# mark1.net
KiCad netlist of a schematic drawn in EAGLE
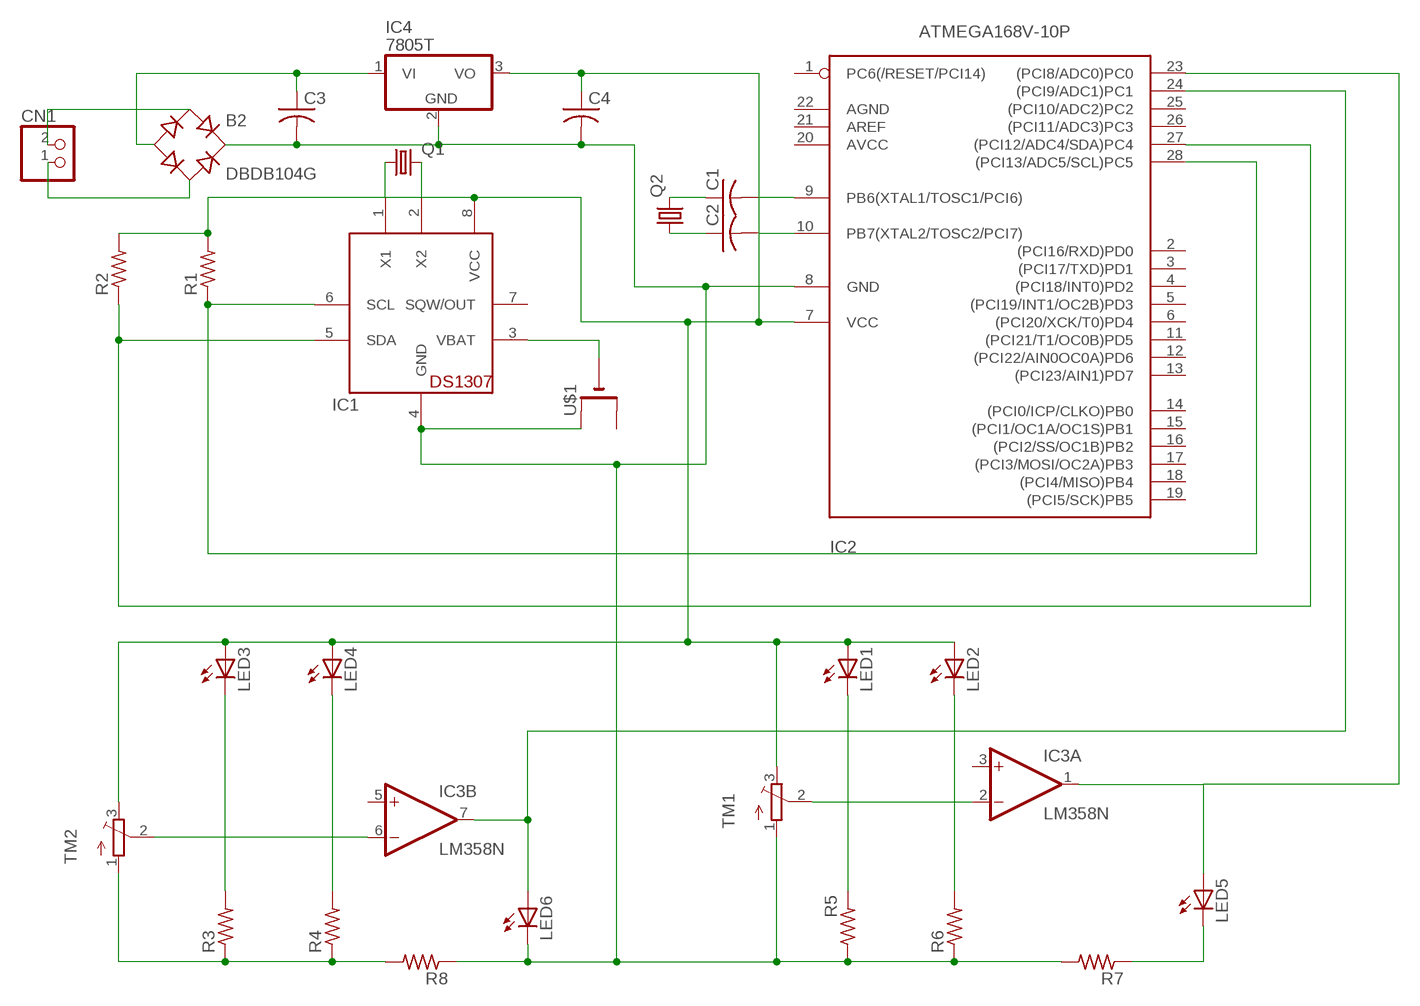
[diagram p0: schematic, sheet 1]

(export (version "E")
  (design (tool "Eeschema 10.0.6"))
  (components
    (comp (ref "B2")
      (value "DBDB104G")
      (footprint "eagle-import:DB")
      (libsource (lib "eagle-import") (part "DB?GDB104"))
    )
    (comp (ref "C1")
      (value "C-US025-024X044")
      (footprint "eagle-import:C025-024X044")
      (libsource (lib "eagle-import") (part "C-US025-024X044"))
    )
    (comp (ref "C2")
      (value "C-US025-024X044")
      (footprint "eagle-import:C025-024X044")
      (libsource (lib "eagle-import") (part "C-US025-024X044"))
    )
    (comp (ref "C3")
      (value "C-US025-024X044")
      (footprint "eagle-import:C025-024X044")
      (libsource (lib "eagle-import") (part "C-US025-024X044"))
    )
    (comp (ref "C4")
      (value "C-US025-024X044")
      (footprint "eagle-import:C025-024X044")
      (libsource (lib "eagle-import") (part "C-US025-024X044"))
    )
    (comp (ref "CN1")
      (value "JST_2PIN-THM")
      (footprint "eagle-import:JST-PH-2-THM")
      (libsource (lib "eagle-import") (part "JST_2PIN-THM"))
    )
    (comp (ref "IC1")
      (value "DS1307")
      (footprint "eagle-import:DIL08")
      (libsource (lib "eagle-import") (part "DS1307"))
    )
    (comp (ref "IC2")
      (value "ATMEGA168V-10P")
      (footprint "eagle-import:DIL28-3")
      (libsource (lib "eagle-import") (part "ATMEGA168PV-10"))
    )
    (comp (ref "IC3")
      (value "LM358N")
      (footprint "eagle-import:DIL08")
      (libsource (lib "eagle-import") (part "LM358N"))
    )
    (comp (ref "IC4")
      (value "7805T")
      (footprint "eagle-import:TO220H")
      (libsource (lib "eagle-import") (part "78T05"))
    )
    (comp (ref "LED1")
      (value "LED5MM")
      (footprint "eagle-import:LED5MM")
      (libsource (lib "eagle-import") (part "LED5MM"))
    )
    (comp (ref "LED2")
      (value "LED5MM")
      (footprint "eagle-import:LED5MM")
      (libsource (lib "eagle-import") (part "LED5MM"))
    )
    (comp (ref "LED3")
      (value "LED5MM")
      (footprint "eagle-import:LED5MM")
      (libsource (lib "eagle-import") (part "LED5MM"))
    )
    (comp (ref "LED4")
      (value "LED5MM")
      (footprint "eagle-import:LED5MM")
      (libsource (lib "eagle-import") (part "LED5MM"))
    )
    (comp (ref "LED5")
      (value "LED5MM")
      (footprint "eagle-import:LED5MM")
      (libsource (lib "eagle-import") (part "LED5MM"))
    )
    (comp (ref "LED6")
      (value "LED5MM")
      (footprint "eagle-import:LED5MM")
      (libsource (lib "eagle-import") (part "LED5MM"))
    )
    (comp (ref "Q1")
      (value "CRYSTALTC26V")
      (footprint "eagle-import:TC26V")
      (libsource (lib "eagle-import") (part "CRYSTALTC26V"))
    )
    (comp (ref "Q2")
      (value "CRYSTALHC33U-V")
      (footprint "eagle-import:HC33U-V")
      (libsource (lib "eagle-import") (part "CRYSTALHC33U-V"))
    )
    (comp (ref "R1")
      (value "R-US_0204/7")
      (footprint "eagle-import:0204_7")
      (libsource (lib "eagle-import") (part "R-US_0204/7"))
    )
    (comp (ref "R2")
      (value "R-US_0204/7")
      (footprint "eagle-import:0204_7")
      (libsource (lib "eagle-import") (part "R-US_0204/7"))
    )
    (comp (ref "R3")
      (value "R-US_0204/7")
      (footprint "eagle-import:0204_7")
      (libsource (lib "eagle-import") (part "R-US_0204/7"))
    )
    (comp (ref "R4")
      (value "R-US_0204/7")
      (footprint "eagle-import:0204_7")
      (libsource (lib "eagle-import") (part "R-US_0204/7"))
    )
    (comp (ref "R5")
      (value "R-US_0204/7")
      (footprint "eagle-import:0204_7")
      (libsource (lib "eagle-import") (part "R-US_0204/7"))
    )
    (comp (ref "R6")
      (value "R-US_0204/7")
      (footprint "eagle-import:0204_7")
      (libsource (lib "eagle-import") (part "R-US_0204/7"))
    )
    (comp (ref "R7")
      (value "R-US_0204/7")
      (footprint "eagle-import:0204_7")
      (libsource (lib "eagle-import") (part "R-US_0204/7"))
    )
    (comp (ref "R8")
      (value "R-US_0204/7")
      (footprint "eagle-import:0204_7")
      (libsource (lib "eagle-import") (part "R-US_0204/7"))
    )
    (comp (ref "TM1")
      (value "TRIMPOT3386")
      (footprint "eagle-import:TRIM-3386")
      (libsource (lib "eagle-import") (part "TRIMPOT3386"))
    )
    (comp (ref "TM2")
      (value "TRIMPOT3386")
      (footprint "eagle-import:TRIM-3386")
      (libsource (lib "eagle-import") (part "TRIMPOT3386"))
    )
    (comp (ref "U$1")
      (value "CR1220THM")
      (footprint "eagle-import:CR1220-THM")
      (libsource (lib "eagle-import") (part "CR1220THM"))
    )
  )
  (nets
    (net (code "1") (name "Net-(C1-Pad1)") (class "Default")
      (node (ref "C1") (pin "1") (pinfunction "1_1") (pintype "passive"))
      (node (ref "Q2") (pin "2") (pinfunction "2_2") (pintype "passive"))
    )
    (net (code "2") (name "Net-(C2-Pad1)") (class "Default")
      (node (ref "C2") (pin "1") (pinfunction "1_1") (pintype "passive"))
      (node (ref "Q2") (pin "1") (pinfunction "1_1") (pintype "passive"))
    )
    (net (code "3") (name "Net-(CN1-1)") (class "Default")
      (node (ref "B2") (pin "AC1") (pinfunction "AC1_AC1") (pintype "passive"))
      (node (ref "CN1") (pin "2") (pinfunction "1_2") (pintype "passive"))
    )
    (net (code "4") (name "Net-(CN1-2)") (class "Default")
      (node (ref "B2") (pin "AC2") (pinfunction "AC2_AC2") (pintype "passive"))
      (node (ref "CN1") (pin "1") (pinfunction "2_1") (pintype "passive"))
    )
    (net (code "5") (name "Net-(IC1-GND)") (class "Default")
      (node (ref "B2") (pin "+") (pinfunction "+_+") (pintype "passive"))
      (node (ref "C3") (pin "2") (pinfunction "2_2") (pintype "passive"))
      (node (ref "C4") (pin "2") (pinfunction "2_2") (pintype "passive"))
      (node (ref "IC1") (pin "4") (pinfunction "GND_4") (pintype "power_in"))
      (node (ref "IC2") (pin "8") (pinfunction "GND_8") (pintype "bidirectional"))
      (node (ref "IC4") (pin "2") (pinfunction "GND_2") (pintype "passive"))
      (node (ref "LED6") (pin "K") (pinfunction "C_K") (pintype "passive"))
      (node (ref "R5") (pin "1") (pinfunction "1_1") (pintype "passive"))
      (node (ref "R6") (pin "1") (pinfunction "1_1") (pintype "passive"))
      (node (ref "R7") (pin "2") (pinfunction "2_2") (pintype "passive"))
      (node (ref "R8") (pin "1") (pinfunction "1_1") (pintype "passive"))
      (node (ref "TM1") (pin "1") (pinfunction "A_1") (pintype "passive"))
      (node (ref "U$1") (pin "+1") (pinfunction "+_+1") (pintype "passive"))
    )
    (net (code "6") (name "Net-(IC1-SCL)") (class "Default")
      (node (ref "IC1") (pin "6") (pinfunction "SCL_6") (pintype "bidirectional"))
      (node (ref "IC2") (pin "28") (pinfunction "(PCI13/ADC5/SCL)PC5_28") (pintype "bidirectional"))
      (node (ref "R1") (pin "1") (pinfunction "1_1") (pintype "passive"))
    )
    (net (code "7") (name "Net-(IC1-SDA)") (class "Default")
      (node (ref "IC1") (pin "5") (pinfunction "SDA_5") (pintype "bidirectional"))
      (node (ref "IC2") (pin "27") (pinfunction "(PCI12/ADC4/SDA)PC4_27") (pintype "bidirectional"))
      (node (ref "R2") (pin "1") (pinfunction "1_1") (pintype "passive"))
    )
    (net (code "8") (name "Net-(IC1-VBAT)") (class "Default")
      (node (ref "IC1") (pin "3") (pinfunction "VBAT_3") (pintype "power_in"))
      (node (ref "U$1") (pin "-") (pinfunction "-_-") (pintype "passive"))
    )
    (net (code "9") (name "Net-(IC1-VCC)") (class "Default")
      (node (ref "C4") (pin "1") (pinfunction "1_1") (pintype "passive"))
      (node (ref "IC1") (pin "8") (pinfunction "VCC_8") (pintype "power_in"))
      (node (ref "IC2") (pin "7") (pinfunction "VCC_7") (pintype "bidirectional"))
      (node (ref "IC4") (pin "3") (pinfunction "VO_3") (pintype "passive"))
      (node (ref "LED1") (pin "A") (pinfunction "A_A") (pintype "passive"))
      (node (ref "LED2") (pin "A") (pinfunction "A_A") (pintype "passive"))
      (node (ref "LED3") (pin "A") (pinfunction "A_A") (pintype "passive"))
      (node (ref "LED4") (pin "A") (pinfunction "A_A") (pintype "passive"))
      (node (ref "R1") (pin "2") (pinfunction "2_2") (pintype "passive"))
      (node (ref "R2") (pin "2") (pinfunction "2_2") (pintype "passive"))
      (node (ref "TM1") (pin "3") (pinfunction "E_3") (pintype "passive"))
      (node (ref "TM2") (pin "3") (pinfunction "E_3") (pintype "passive"))
    )
    (net (code "10") (name "Net-(IC1-X1)") (class "Default")
      (node (ref "IC1") (pin "1") (pinfunction "X1_1") (pintype "passive"))
      (node (ref "Q1") (pin "1") (pinfunction "1_1") (pintype "passive"))
    )
    (net (code "11") (name "Net-(IC1-X2)") (class "Default")
      (node (ref "IC1") (pin "2") (pinfunction "X2_2") (pintype "passive"))
      (node (ref "Q1") (pin "2") (pinfunction "2_2") (pintype "passive"))
    )
    (net (code "12") (name "Net-(IC2-(PCI8{slash}ADC0)PC0)") (class "Default")
      (node (ref "IC2") (pin "23") (pinfunction "(PCI8/ADC0)PC0_23") (pintype "bidirectional"))
      (node (ref "IC3") (pin "1") (pinfunction "OUT_1") (pintype "output"))
      (node (ref "LED5") (pin "A") (pinfunction "A_A") (pintype "passive"))
    )
    (net (code "13") (name "Net-(IC2-(PCI9{slash}ADC1)PC1)") (class "Default")
      (node (ref "IC2") (pin "24") (pinfunction "(PCI9/ADC1)PC1_24") (pintype "bidirectional"))
      (node (ref "IC3") (pin "7") (pinfunction "OUT_7") (pintype "output"))
      (node (ref "LED6") (pin "A") (pinfunction "A_A") (pintype "passive"))
    )
    (net (code "14") (name "Net-(IC2-PB6(XTAL1{slash}TOSC1{slash}PCI6))") (class "Default")
      (node (ref "C1") (pin "2") (pinfunction "2_2") (pintype "passive"))
      (node (ref "IC2") (pin "9") (pinfunction "PB6(XTAL1/TOSC1/PCI6)_9") (pintype "bidirectional"))
    )
    (net (code "15") (name "Net-(IC2-PB7(XTAL2{slash}TOSC2{slash}PCI7))") (class "Default")
      (node (ref "C2") (pin "2") (pinfunction "2_2") (pintype "passive"))
      (node (ref "IC2") (pin "10") (pinfunction "PB7(XTAL2/TOSC2/PCI7)_10") (pintype "bidirectional"))
    )
    (net (code "16") (name "Net-(IC3A--IN)") (class "Default")
      (node (ref "IC3") (pin "2") (pinfunction "-IN_2") (pintype "input"))
      (node (ref "TM1") (pin "2") (pinfunction "S_2") (pintype "passive"))
    )
    (net (code "17") (name "Net-(IC3B--IN)") (class "Default")
      (node (ref "IC3") (pin "6") (pinfunction "-IN_6") (pintype "input"))
      (node (ref "TM2") (pin "2") (pinfunction "S_2") (pintype "passive"))
    )
    (net (code "18") (name "Net-(IC4-VI)") (class "Default")
      (node (ref "B2") (pin "-") (pinfunction "-_-") (pintype "passive"))
      (node (ref "C3") (pin "1") (pinfunction "1_1") (pintype "passive"))
      (node (ref "IC4") (pin "1") (pinfunction "VI_1") (pintype "input"))
    )
    (net (code "19") (name "Net-(LED1-C)") (class "Default")
      (node (ref "LED1") (pin "K") (pinfunction "C_K") (pintype "passive"))
      (node (ref "R5") (pin "2") (pinfunction "2_2") (pintype "passive"))
    )
    (net (code "20") (name "Net-(LED2-C)") (class "Default")
      (node (ref "LED2") (pin "K") (pinfunction "C_K") (pintype "passive"))
      (node (ref "R6") (pin "2") (pinfunction "2_2") (pintype "passive"))
    )
    (net (code "21") (name "Net-(LED3-C)") (class "Default")
      (node (ref "LED3") (pin "K") (pinfunction "C_K") (pintype "passive"))
      (node (ref "R3") (pin "2") (pinfunction "2_2") (pintype "passive"))
    )
    (net (code "22") (name "Net-(LED4-C)") (class "Default")
      (node (ref "LED4") (pin "K") (pinfunction "C_K") (pintype "passive"))
      (node (ref "R4") (pin "2") (pinfunction "2_2") (pintype "passive"))
    )
    (net (code "23") (name "Net-(LED5-C)") (class "Default")
      (node (ref "LED5") (pin "K") (pinfunction "C_K") (pintype "passive"))
      (node (ref "R7") (pin "1") (pinfunction "1_1") (pintype "passive"))
    )
    (net (code "24") (name "Net-(TM2-A)") (class "Default")
      (node (ref "R3") (pin "1") (pinfunction "1_1") (pintype "passive"))
      (node (ref "R4") (pin "1") (pinfunction "1_1") (pintype "passive"))
      (node (ref "R8") (pin "2") (pinfunction "2_2") (pintype "passive"))
      (node (ref "TM2") (pin "1") (pinfunction "A_1") (pintype "passive"))
    )
    (net (code "25") (name "unconnected-(IC1-SQW{slash}OUT-Pad7)") (class "Default")
      (node (ref "IC1") (pin "7") (pinfunction "SQW/OUT_7") (pintype "bidirectional"))
    )
    (net (code "26") (name "unconnected-(IC2-(PCI0{slash}ICP{slash}CLKO)PB0-Pad14)") (class "Default")
      (node (ref "IC2") (pin "14") (pinfunction "(PCI0/ICP/CLKO)PB0_14") (pintype "bidirectional"))
    )
    (net (code "27") (name "unconnected-(IC2-(PCI1{slash}OC1A{slash}OC1S)PB1-Pad15)") (class "Default")
      (node (ref "IC2") (pin "15") (pinfunction "(PCI1/OC1A/OC1S)PB1_15") (pintype "bidirectional"))
    )
    (net (code "28") (name "unconnected-(IC2-(PCI2{slash}SS{slash}OC1B)PB2-Pad16)") (class "Default")
      (node (ref "IC2") (pin "16") (pinfunction "(PCI2/SS/OC1B)PB2_16") (pintype "bidirectional"))
    )
    (net (code "29") (name "unconnected-(IC2-(PCI3{slash}MOSI{slash}OC2A)PB3-Pad17)") (class "Default")
      (node (ref "IC2") (pin "17") (pinfunction "(PCI3/MOSI/OC2A)PB3_17") (pintype "bidirectional"))
    )
    (net (code "30") (name "unconnected-(IC2-(PCI4{slash}MISO)PB4-Pad18)") (class "Default")
      (node (ref "IC2") (pin "18") (pinfunction "(PCI4/MISO)PB4_18") (pintype "bidirectional"))
    )
    (net (code "31") (name "unconnected-(IC2-(PCI5{slash}SCK)PB5-Pad19)") (class "Default")
      (node (ref "IC2") (pin "19") (pinfunction "(PCI5/SCK)PB5_19") (pintype "bidirectional"))
    )
    (net (code "32") (name "unconnected-(IC2-(PCI10{slash}ADC2)PC2-Pad25)") (class "Default")
      (node (ref "IC2") (pin "25") (pinfunction "(PCI10/ADC2)PC2_25") (pintype "bidirectional"))
    )
    (net (code "33") (name "unconnected-(IC2-(PCI11{slash}ADC3)PC3-Pad26)") (class "Default")
      (node (ref "IC2") (pin "26") (pinfunction "(PCI11/ADC3)PC3_26") (pintype "bidirectional"))
    )
    (net (code "34") (name "unconnected-(IC2-(PCI16{slash}RXD)PD0-Pad2)") (class "Default")
      (node (ref "IC2") (pin "2") (pinfunction "(PCI16/RXD)PD0_2") (pintype "bidirectional"))
    )
    (net (code "35") (name "unconnected-(IC2-(PCI17{slash}TXD)PD1-Pad3)") (class "Default")
      (node (ref "IC2") (pin "3") (pinfunction "(PCI17/TXD)PD1_3") (pintype "bidirectional"))
    )
    (net (code "36") (name "unconnected-(IC2-(PCI18{slash}INT0)PD2-Pad4)") (class "Default")
      (node (ref "IC2") (pin "4") (pinfunction "(PCI18/INT0)PD2_4") (pintype "bidirectional"))
    )
    (net (code "37") (name "unconnected-(IC2-(PCI19{slash}INT1{slash}OC2B)PD3-Pad5)") (class "Default")
      (node (ref "IC2") (pin "5") (pinfunction "(PCI19/INT1/OC2B)PD3_5") (pintype "bidirectional"))
    )
    (net (code "38") (name "unconnected-(IC2-(PCI20{slash}XCK{slash}T0)PD4-Pad6)") (class "Default")
      (node (ref "IC2") (pin "6") (pinfunction "(PCI20/XCK/T0)PD4_6") (pintype "bidirectional"))
    )
    (net (code "39") (name "unconnected-(IC2-(PCI21{slash}T1{slash}OC0B)PD5-Pad11)") (class "Default")
      (node (ref "IC2") (pin "11") (pinfunction "(PCI21/T1/OC0B)PD5_11") (pintype "bidirectional"))
    )
    (net (code "40") (name "unconnected-(IC2-(PCI22{slash}AIN0OC0A)PD6-Pad12)") (class "Default")
      (node (ref "IC2") (pin "12") (pinfunction "(PCI22/AIN0OC0A)PD6_12") (pintype "bidirectional"))
    )
    (net (code "41") (name "unconnected-(IC2-(PCI23{slash}AIN1)PD7-Pad13)") (class "Default")
      (node (ref "IC2") (pin "13") (pinfunction "(PCI23/AIN1)PD7_13") (pintype "bidirectional"))
    )
    (net (code "42") (name "unconnected-(IC2-AGND-Pad22)") (class "Default")
      (node (ref "IC2") (pin "22") (pinfunction "AGND_22") (pintype "bidirectional"))
    )
    (net (code "43") (name "unconnected-(IC2-AREF-Pad21)") (class "Default")
      (node (ref "IC2") (pin "21") (pinfunction "AREF_21") (pintype "bidirectional"))
    )
    (net (code "44") (name "unconnected-(IC2-AVCC-Pad20)") (class "Default")
      (node (ref "IC2") (pin "20") (pinfunction "AVCC_20") (pintype "bidirectional"))
    )
    (net (code "45") (name "unconnected-(IC2-PC6({slash}RESET{slash}PCI14)-Pad1)") (class "Default")
      (node (ref "IC2") (pin "1") (pinfunction "PC6(/RESET/PCI14)_1") (pintype "bidirectional"))
    )
    (net (code "46") (name "unconnected-(IC3A-+IN-Pad3)") (class "Default")
      (node (ref "IC3") (pin "3") (pinfunction "+IN_3") (pintype "input"))
    )
    (net (code "47") (name "unconnected-(IC3B-+IN-Pad5)") (class "Default")
      (node (ref "IC3") (pin "5") (pinfunction "+IN_5") (pintype "input"))
    )
    (net (code "48") (name "unconnected-(U$1-+1-Pad+2)") (class "Default")
      (node (ref "U$1") (pin "+2") (pinfunction "+1_+2") (pintype "passive"))
    )
  )
)
